# SMC_FrontPanel_ExtensionBoard_Step2_V14_.net
KiCad netlist of a schematic drawn in EAGLE
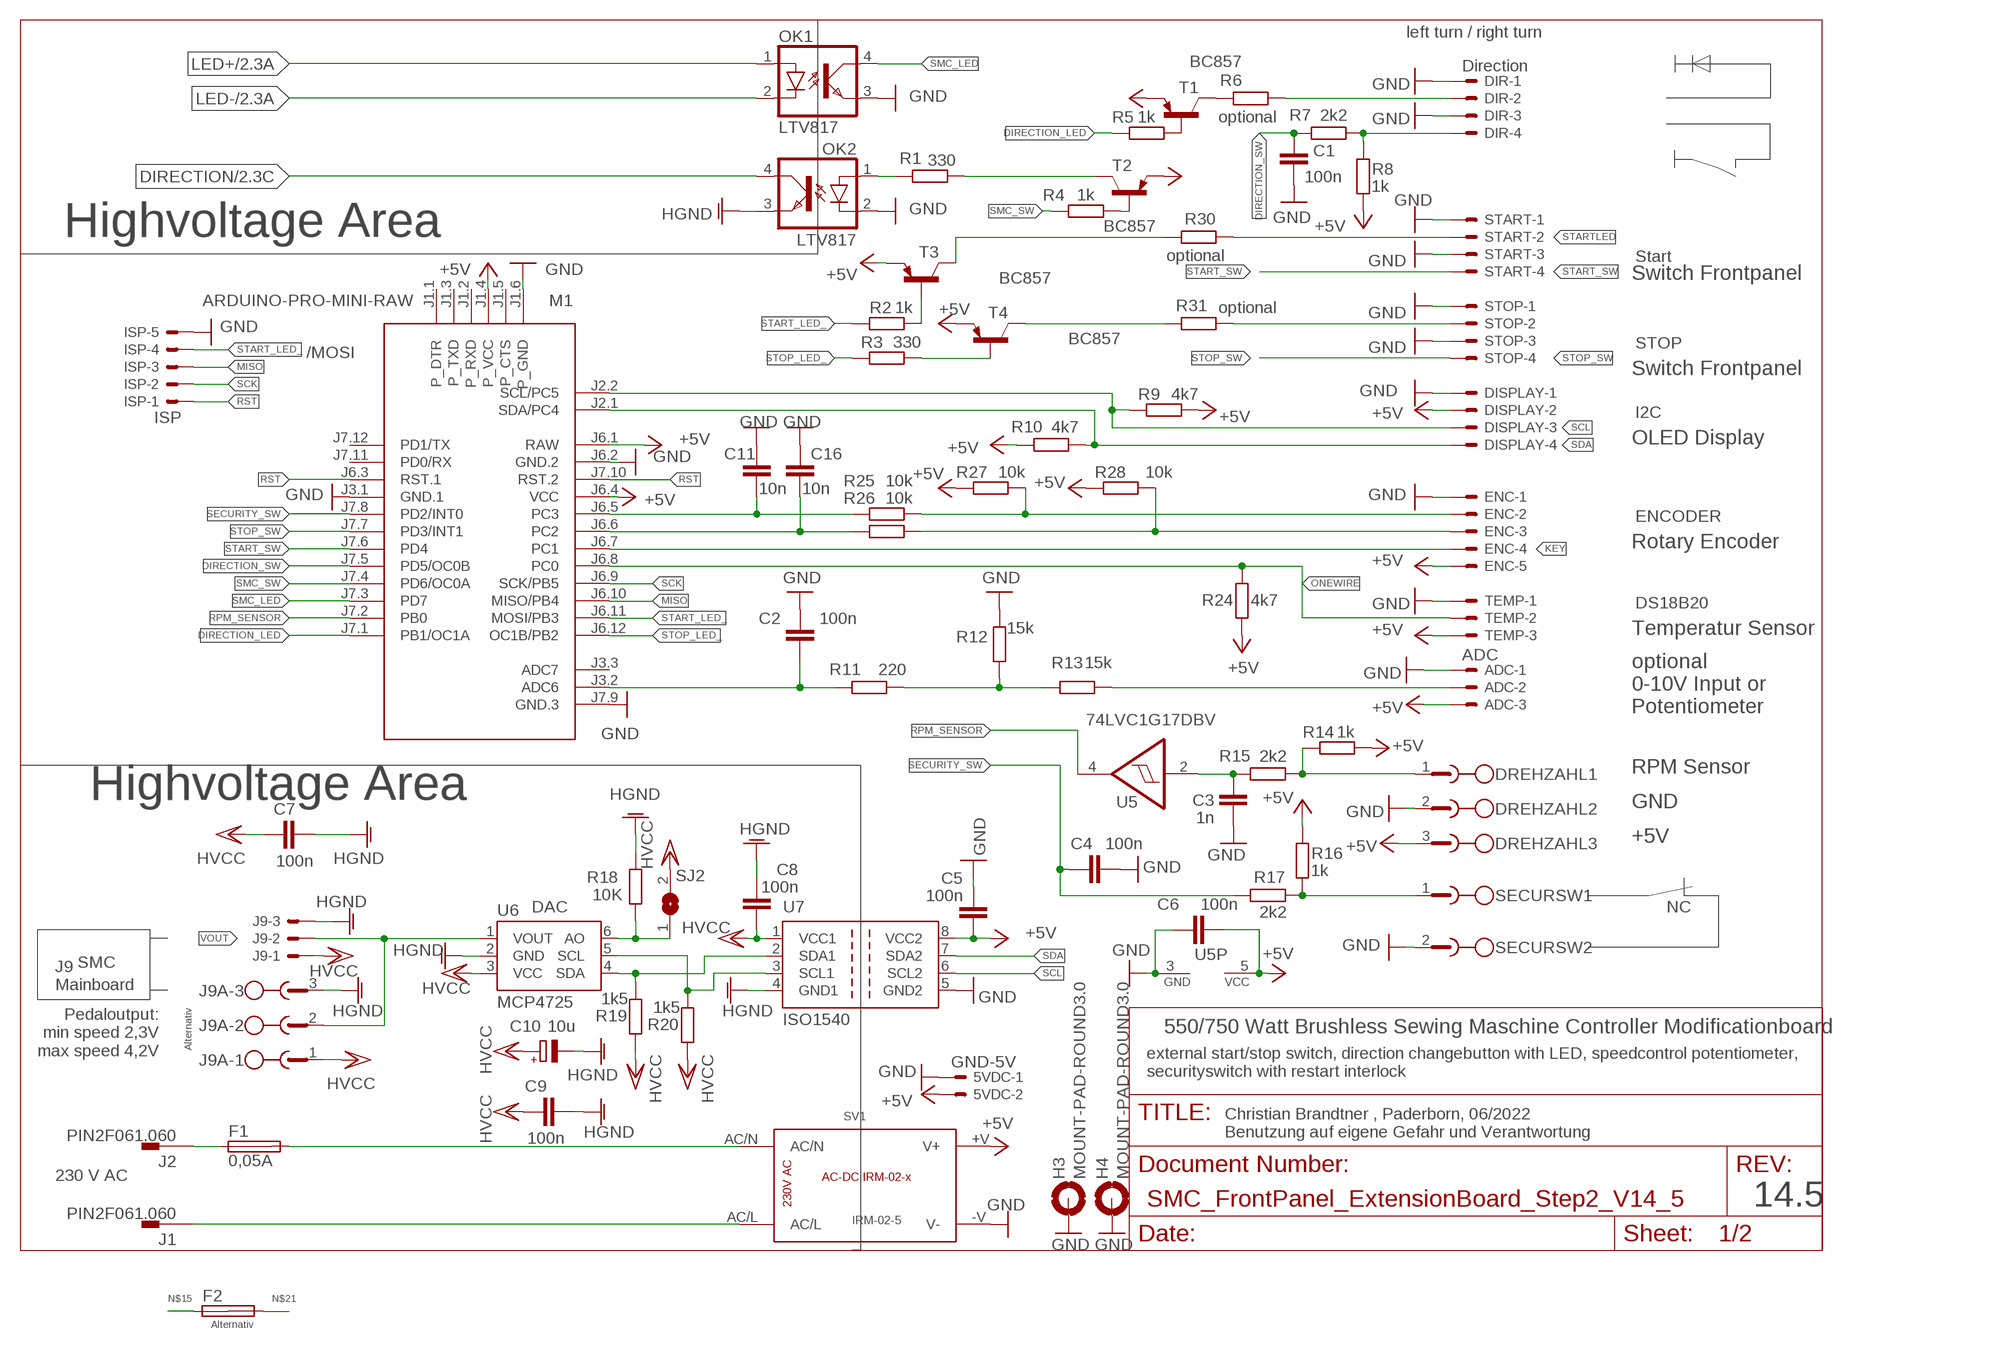
[diagram p0: schematic, sheet 1]
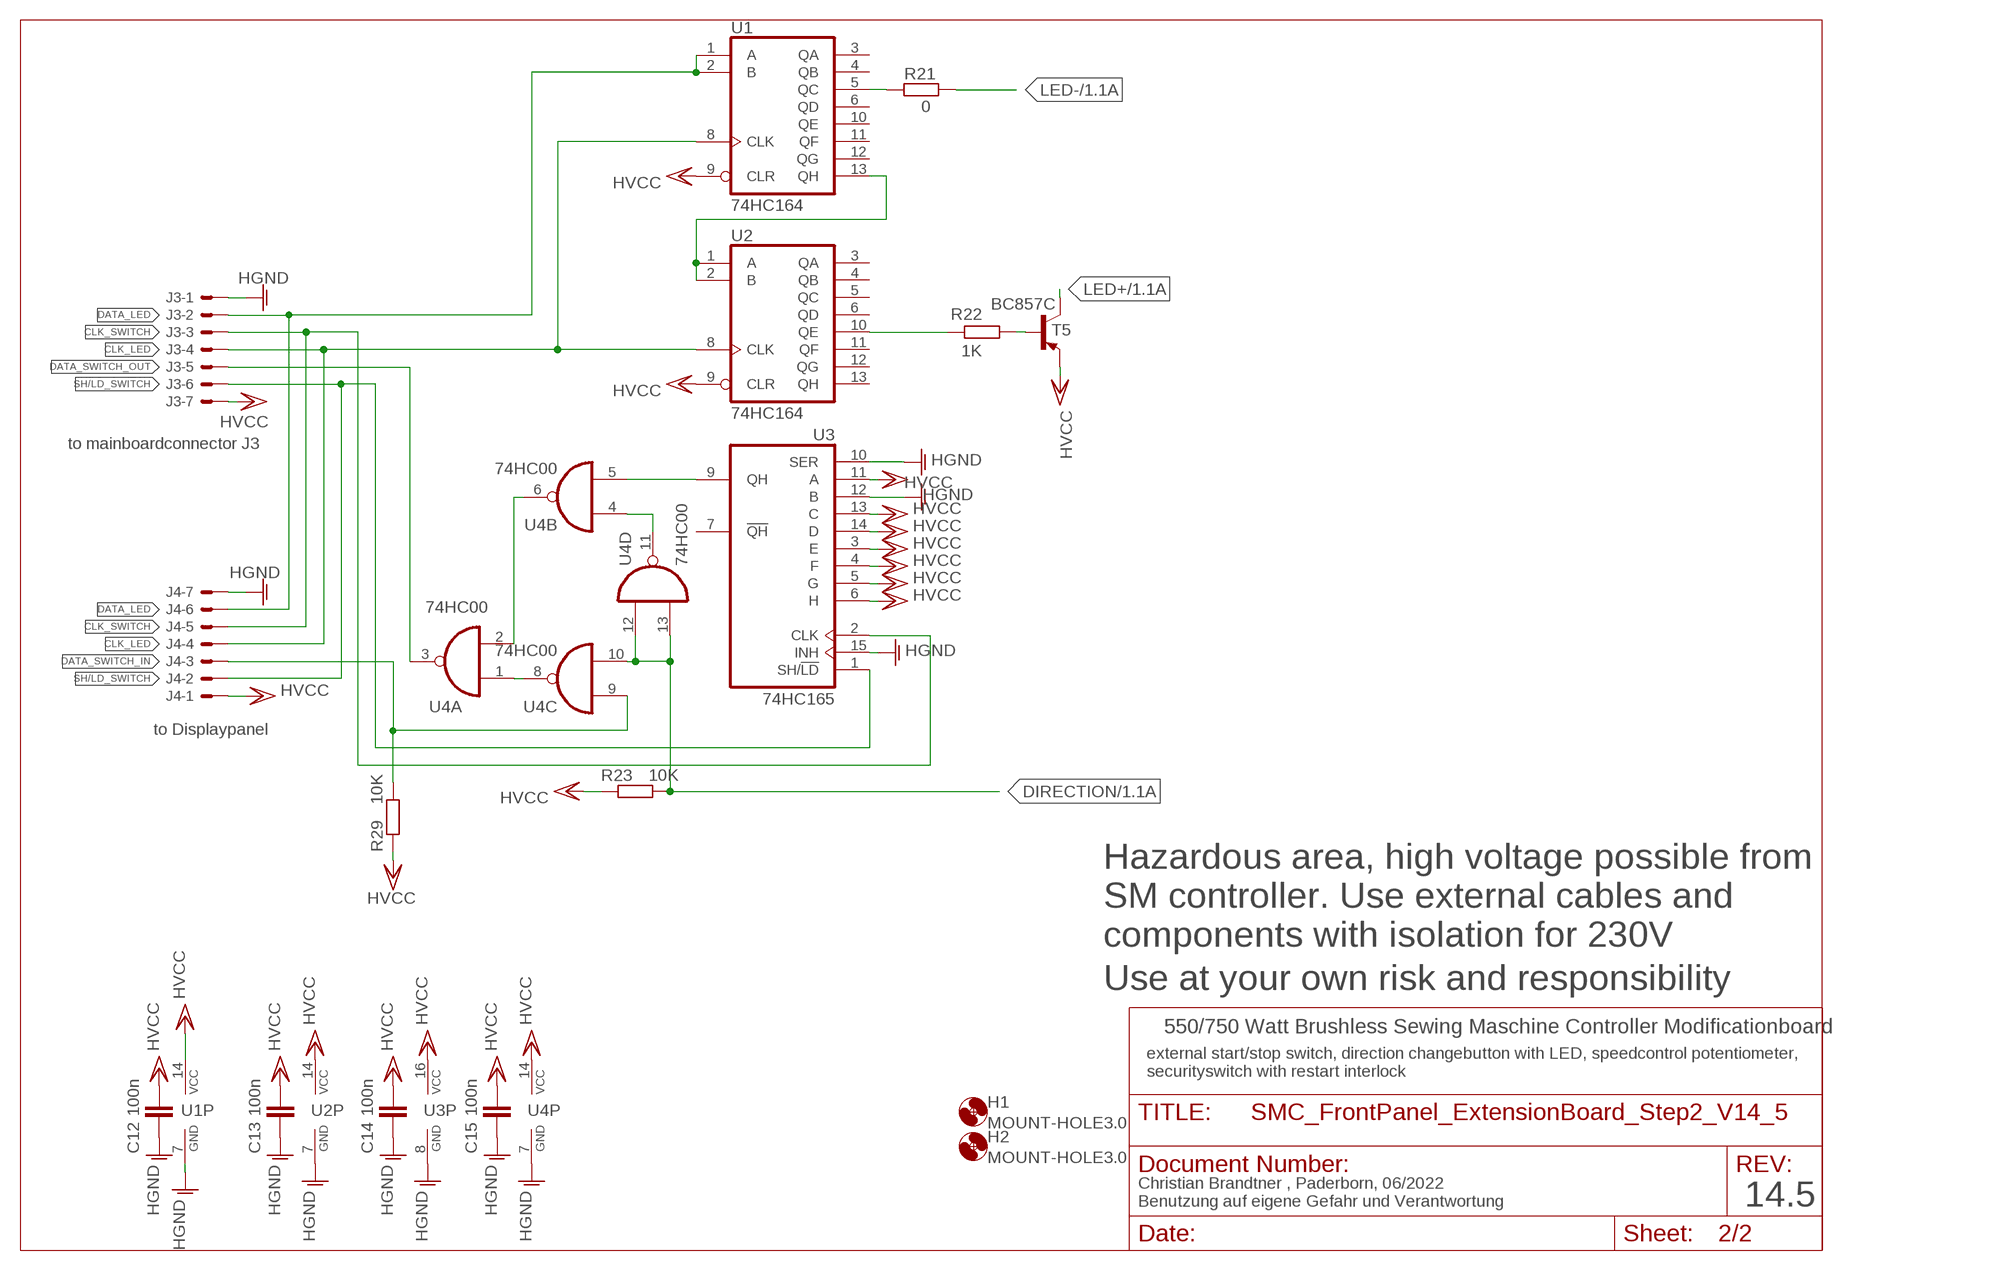
[diagram p1: schematic, sheet 2]

(export (version "E")
  (design (tool "Eeschema 10.0.6"))
  (components
    (comp (ref "C12")
      (value "100n")
      (footprint "eagle-import:C0805")
      (libsource (lib "eagle-import") (part "C-EUC0805"))
    )
    (comp (ref "C13")
      (value "100n")
      (footprint "eagle-import:C0805")
      (libsource (lib "eagle-import") (part "C-EUC0805"))
    )
    (comp (ref "C14")
      (value "100n")
      (footprint "eagle-import:C0805")
      (libsource (lib "eagle-import") (part "C-EUC0805"))
    )
    (comp (ref "C15")
      (value "100n")
      (footprint "eagle-import:C0805")
      (libsource (lib "eagle-import") (part "C-EUC0805"))
    )
    (comp (ref "H1")
      (value "MOUNT-HOLE3.0")
      (footprint "eagle-import:3,0")
      (libsource (lib "eagle-import") (part "MOUNT-HOLE3.0"))
    )
    (comp (ref "H2")
      (value "MOUNT-HOLE3.0")
      (footprint "eagle-import:3,0")
      (libsource (lib "eagle-import") (part "MOUNT-HOLE3.0"))
    )
    (comp (ref "J3")
      (value "to mainboardconnector J3")
      (footprint "eagle-import:JST-XH-07-PACKAGE-ROUND-PAD")
      (libsource (lib "eagle-import") (part "JST-XH-07-PIN-ROUND-PAD"))
    )
    (comp (ref "J4")
      (value "to Displaypanel")
      (footprint "eagle-import:JST-XH-07-PACKAGE-ROUND-PAD")
      (libsource (lib "eagle-import") (part "JST-XH-07-PIN-ROUND-PAD"))
    )
    (comp (ref "R21")
      (value "0")
      (footprint "eagle-import:R0805")
      (libsource (lib "eagle-import") (part "R-EU_R0805"))
    )
    (comp (ref "R22")
      (value "1K")
      (footprint "eagle-import:R0805")
      (libsource (lib "eagle-import") (part "R-EU_R0805"))
    )
    (comp (ref "R23")
      (value "10K")
      (footprint "eagle-import:R0805")
      (libsource (lib "eagle-import") (part "R-EU_R0805"))
    )
    (comp (ref "R29")
      (value "10K")
      (footprint "eagle-import:R0805")
      (libsource (lib "eagle-import") (part "R-EU_R0805"))
    )
    (comp (ref "T5")
      (value "BC857C")
      (footprint "eagle-import:SOT23-BEC")
      (libsource (lib "eagle-import") (part "-PNP-SOT23-BECBC857C"))
    )
    (comp (ref "U1")
      (value "74HC164")
      (footprint "eagle-import:SO14")
      (libsource (lib "eagle-import") (part "74164DHC"))
    )
    (comp (ref "U2")
      (value "74HC164")
      (footprint "eagle-import:SO14")
      (libsource (lib "eagle-import") (part "74164DHC"))
    )
    (comp (ref "U3")
      (value "74HC165")
      (footprint "eagle-import:SO16")
      (libsource (lib "eagle-import") (part "74165DHC"))
    )
    (comp (ref "U4")
      (value "74HC00")
      (footprint "eagle-import:SO14")
      (libsource (lib "eagle-import") (part "7400DHC"))
    )
    (comp (ref "5VDC")
      (value "GND-5V")
      (footprint "eagle-import:JST-XH-02-PACKAGE-ROUND-PAD")
      (libsource (lib "eagle-import") (part "JST-XH-02-PIN-ROUND-PAD"))
    )
    (comp (ref "ADC")
      (value "ADC")
      (footprint "eagle-import:JST-XH-03-PACKAGE-ROUND-PAD")
      (libsource (lib "eagle-import") (part "JST-XH-03-PIN-ROUND-PAD"))
    )
    (comp (ref "C1")
      (value "100n")
      (footprint "eagle-import:C0805")
      (libsource (lib "eagle-import") (part "C-EUC0805"))
    )
    (comp (ref "C2")
      (value "100n")
      (footprint "eagle-import:C0805")
      (libsource (lib "eagle-import") (part "C-EUC0805"))
    )
    (comp (ref "C3")
      (value "1n")
      (footprint "eagle-import:C0805")
      (libsource (lib "eagle-import") (part "C-EUC0805"))
    )
    (comp (ref "C4")
      (value "100n")
      (footprint "eagle-import:C0805")
      (libsource (lib "eagle-import") (part "C-EUC0805"))
    )
    (comp (ref "C5")
      (value "100n")
      (footprint "eagle-import:C0805")
      (libsource (lib "eagle-import") (part "C-EUC0805"))
    )
    (comp (ref "C6")
      (value "100n")
      (footprint "eagle-import:C0805")
      (libsource (lib "eagle-import") (part "C-EUC0805"))
    )
    (comp (ref "C7")
      (value "100n")
      (footprint "eagle-import:C0805")
      (libsource (lib "eagle-import") (part "C-EUC0805"))
    )
    (comp (ref "C8")
      (value "100n")
      (footprint "eagle-import:C0805")
      (libsource (lib "eagle-import") (part "C-EUC0805"))
    )
    (comp (ref "C9")
      (value "100n")
      (footprint "eagle-import:C0805")
      (libsource (lib "eagle-import") (part "C-EUC0805"))
    )
    (comp (ref "C10")
      (value "10u")
      (footprint "eagle-import:153CLV-0405")
      (libsource (lib "eagle-import") (part "CPOL-EU153CLV-0405"))
    )
    (comp (ref "C11")
      (value "10n")
      (footprint "eagle-import:C0805")
      (libsource (lib "eagle-import") (part "C-EUC0805"))
    )
    (comp (ref "C16")
      (value "10n")
      (footprint "eagle-import:C0805")
      (libsource (lib "eagle-import") (part "C-EUC0805"))
    )
    (comp (ref "DIR")
      (value "Direction")
      (footprint "eagle-import:JST-XH-04-PACKAGE-ROUND-PAD")
      (libsource (lib "eagle-import") (part "JST-XH-04-PIN-ROUND-PAD"))
    )
    (comp (ref "DISPLAY")
      (value "I2C")
      (footprint "eagle-import:JST-XH-04-PACKAGE-ROUND-PAD")
      (libsource (lib "eagle-import") (part "JST-XH-04-PIN-ROUND-PAD"))
    )
    (comp (ref "DREHZAHL")
      (value "MCV_1.5/3/-G-3.5")
      (footprint "eagle-import:1843619")
      (libsource (lib "eagle-import") (part "MCV_1.5/3/-G-3.5"))
    )
    (comp (ref "ENC")
      (value "ENCODER")
      (footprint "eagle-import:JST-XH-05-PACKAGE-ROUND-PAD")
      (libsource (lib "eagle-import") (part "JST-XH-05-PIN-ROUND-PAD"))
    )
    (comp (ref "F1")
      (value "0,05A")
      (footprint "eagle-import:MTA501100")
      (libsource (lib "eagle-import") (part "FUSE"))
    )
    (comp (ref "F2")
      (value "SHK20L")
      (footprint "eagle-import:SHK20L")
      (libsource (lib "eagle-import") (part "SHK20L"))
    )
    (comp (ref "H3")
      (value "MOUNT-PAD-ROUND3.0")
      (footprint "eagle-import:3,0-PAD")
      (libsource (lib "eagle-import") (part "MOUNT-PAD-ROUND3.0"))
    )
    (comp (ref "H4")
      (value "MOUNT-PAD-ROUND3.0")
      (footprint "eagle-import:3,0-PAD")
      (libsource (lib "eagle-import") (part "MOUNT-PAD-ROUND3.0"))
    )
    (comp (ref "ISP")
      (value "ISP")
      (footprint "eagle-import:JST-XH-05-PACKAGE-ROUND-PAD")
      (libsource (lib "eagle-import") (part "JST-XH-05-PIN-ROUND-PAD"))
    )
    (comp (ref "J1")
      (value "PIN2F061.060")
      (footprint "eagle-import:F061.060")
      (libsource (lib "eagle-import") (part "PIN2F061.060"))
    )
    (comp (ref "J2")
      (value "PIN2F061.060")
      (footprint "eagle-import:F061.060")
      (libsource (lib "eagle-import") (part "PIN2F061.060"))
    )
    (comp (ref "J9")
      (value "JST-XH-03-PIN-ROUND-PAD")
      (footprint "eagle-import:JST-XH-03-PACKAGE-ROUND-PAD")
      (libsource (lib "eagle-import") (part "JST-XH-03-PIN-ROUND-PAD"))
    )
    (comp (ref "J9A-")
      (value "MCV_1.5/3/-G-3.5")
      (footprint "eagle-import:1843619")
      (libsource (lib "eagle-import") (part "MCV_1.5/3/-G-3.5"))
    )
    (comp (ref "M1")
      (value "ARDUINO-PRO-MINI-RAW")
      (footprint "eagle-import:ARDUINO-PRO-MINI")
      (libsource (lib "eagle-import") (part "ARDUINO-PRO-MINI-RAW"))
    )
    (comp (ref "OK1")
      (value "LTV817")
      (footprint "eagle-import:SMD4-7")
      (fields (field (name "MF") "VISHAY/TELEFUNKEN") (field (name "MPN") "SFH6186-2"))
      (libsource (lib "eagle-import") (part "SFH618?6-2"))
    )
    (comp (ref "OK2")
      (value "LTV817")
      (footprint "eagle-import:SMD4-7")
      (fields (field (name "MF") "VISHAY/TELEFUNKEN") (field (name "MPN") "SFH6186-2"))
      (libsource (lib "eagle-import") (part "SFH618?6-2"))
    )
    (comp (ref "R1")
      (value "330")
      (footprint "eagle-import:R0805")
      (libsource (lib "eagle-import") (part "R-EU_R0805"))
    )
    (comp (ref "R2")
      (value "1k")
      (footprint "eagle-import:R0805")
      (libsource (lib "eagle-import") (part "R-EU_R0805"))
    )
    (comp (ref "R3")
      (value "330")
      (footprint "eagle-import:R0805")
      (libsource (lib "eagle-import") (part "R-EU_R0805"))
    )
    (comp (ref "R4")
      (value "1k")
      (footprint "eagle-import:R0805")
      (libsource (lib "eagle-import") (part "R-EU_R0805"))
    )
    (comp (ref "R5")
      (value "1k")
      (footprint "eagle-import:R0805")
      (libsource (lib "eagle-import") (part "R-EU_R0805"))
    )
    (comp (ref "R6")
      (value "optional")
      (footprint "eagle-import:R0805")
      (libsource (lib "eagle-import") (part "R-EU_R0805"))
    )
    (comp (ref "R7")
      (value "2k2")
      (footprint "eagle-import:R0805")
      (libsource (lib "eagle-import") (part "R-EU_R0805"))
    )
    (comp (ref "R8")
      (value "1k")
      (footprint "eagle-import:R0805")
      (libsource (lib "eagle-import") (part "R-EU_R0805"))
    )
    (comp (ref "R9")
      (value "4k7")
      (footprint "eagle-import:R0805")
      (libsource (lib "eagle-import") (part "R-EU_R0805"))
    )
    (comp (ref "R10")
      (value "4k7")
      (footprint "eagle-import:R0805")
      (libsource (lib "eagle-import") (part "R-EU_R0805"))
    )
    (comp (ref "R11")
      (value "220")
      (footprint "eagle-import:R0805")
      (libsource (lib "eagle-import") (part "R-EU_R0805"))
    )
    (comp (ref "R12")
      (value "15k")
      (footprint "eagle-import:R0805")
      (libsource (lib "eagle-import") (part "R-EU_R0805"))
    )
    (comp (ref "R13")
      (value "15k")
      (footprint "eagle-import:R0805")
      (libsource (lib "eagle-import") (part "R-EU_R0805"))
    )
    (comp (ref "R14")
      (value "1k")
      (footprint "eagle-import:R0805")
      (libsource (lib "eagle-import") (part "R-EU_R0805"))
    )
    (comp (ref "R15")
      (value "2k2")
      (footprint "eagle-import:R0805")
      (libsource (lib "eagle-import") (part "R-EU_R0805"))
    )
    (comp (ref "R16")
      (value "1k")
      (footprint "eagle-import:R0805")
      (libsource (lib "eagle-import") (part "R-EU_R0805"))
    )
    (comp (ref "R17")
      (value "2k2")
      (footprint "eagle-import:R0805")
      (libsource (lib "eagle-import") (part "R-EU_R0805"))
    )
    (comp (ref "R18")
      (value "10K")
      (footprint "eagle-import:R0805")
      (libsource (lib "eagle-import") (part "R-EU_R0805"))
    )
    (comp (ref "R19")
      (value "1k5")
      (footprint "eagle-import:R0805")
      (libsource (lib "eagle-import") (part "R-EU_R0805"))
    )
    (comp (ref "R20")
      (value "1k5")
      (footprint "eagle-import:R0805")
      (libsource (lib "eagle-import") (part "R-EU_R0805"))
    )
    (comp (ref "R24")
      (value "4k7")
      (footprint "eagle-import:R0805")
      (libsource (lib "eagle-import") (part "R-EU_R0805"))
    )
    (comp (ref "R25")
      (value "10k")
      (footprint "eagle-import:R0805")
      (libsource (lib "eagle-import") (part "R-EU_R0805"))
    )
    (comp (ref "R26")
      (value "10k")
      (footprint "eagle-import:R0805")
      (libsource (lib "eagle-import") (part "R-EU_R0805"))
    )
    (comp (ref "R27")
      (value "10k")
      (footprint "eagle-import:R0805")
      (libsource (lib "eagle-import") (part "R-EU_R0805"))
    )
    (comp (ref "R28")
      (value "10k")
      (footprint "eagle-import:R0805")
      (libsource (lib "eagle-import") (part "R-EU_R0805"))
    )
    (comp (ref "R30")
      (value "optional")
      (footprint "eagle-import:R0805")
      (libsource (lib "eagle-import") (part "R-EU_R0805"))
    )
    (comp (ref "R31")
      (value "optional")
      (footprint "eagle-import:R0805")
      (libsource (lib "eagle-import") (part "R-EU_R0805"))
    )
    (comp (ref "SECURSW")
      (value "MCV_1,5/2-G-3,5")
      (footprint "eagle-import:1843606")
      (libsource (lib "eagle-import") (part "MCV_1,5/2-G-3,5"))
    )
    (comp (ref "SJ2") (value "SJ") (footprint "eagle-import:SJ") (libsource (lib "eagle-import") (part "SJ")))
    (comp (ref "START")
      (value "Start")
      (footprint "eagle-import:JST-XH-04-PACKAGE-ROUND-PAD")
      (libsource (lib "eagle-import") (part "JST-XH-04-PIN-ROUND-PAD"))
    )
    (comp (ref "STOP")
      (value "STOP")
      (footprint "eagle-import:JST-XH-04-PACKAGE-ROUND-PAD")
      (libsource (lib "eagle-import") (part "JST-XH-04-PIN-ROUND-PAD"))
    )
    (comp (ref "SV1")
      (value "IRM-02-5")
      (footprint "eagle-import:IRM-02-X")
      (libsource (lib "eagle-import") (part "IRM-02-X"))
    )
    (comp (ref "T1")
      (value "BC857")
      (footprint "eagle-import:SOT23-BEC")
      (libsource (lib "eagle-import") (part "BC857SMDA"))
    )
    (comp (ref "T2")
      (value "BC857")
      (footprint "eagle-import:SOT23-BEC")
      (libsource (lib "eagle-import") (part "BC857SMDA"))
    )
    (comp (ref "T3")
      (value "BC857")
      (footprint "eagle-import:SOT23-BEC")
      (libsource (lib "eagle-import") (part "BC857SMDA"))
    )
    (comp (ref "T4")
      (value "BC857")
      (footprint "eagle-import:SOT23-BEC")
      (libsource (lib "eagle-import") (part "BC857SMDA"))
    )
    (comp (ref "TEMP")
      (value "DS18B20")
      (footprint "eagle-import:JST-XH-03-PACKAGE-ROUND-PAD")
      (libsource (lib "eagle-import") (part "JST-XH-03-PIN-ROUND-PAD"))
    )
    (comp (ref "U5")
      (value "74LVC1G17DBV")
      (footprint "eagle-import:SOT23-5")
      (libsource (lib "eagle-import") (part "741G17DBVLVC"))
    )
    (comp (ref "U6")
      (value "MCP4725")
      (footprint "eagle-import:SOT23-6")
      (libsource (lib "eagle-import") (part "MCP4725SOT-23"))
    )
    (comp (ref "U7")
      (value "ISO1540")
      (footprint "eagle-import:SO-08")
      (libsource (lib "eagle-import") (part "ISO1540"))
    )
  )
  (nets
    (net (code "1") (name "+5V") (class "Default")
      (node (ref "5VDC") (pin "2") (pinfunction "S_2") (pintype "passive"))
      (node (ref "ADC") (pin "3") (pinfunction "S_3") (pintype "passive"))
      (node (ref "C5") (pin "1") (pinfunction "1_1") (pintype "passive"))
      (node (ref "C6") (pin "1") (pinfunction "1_1") (pintype "passive"))
      (node (ref "DISPLAY") (pin "2") (pinfunction "S_2") (pintype "passive"))
      (node (ref "DREHZAHL") (pin "3") (pinfunction "1_3") (pintype "passive"))
      (node (ref "ENC") (pin "5") (pinfunction "S_5") (pintype "passive"))
      (node (ref "M1") (pin "J1.4") (pinfunction "P_VCC_J1.4") (pintype "bidirectional"))
      (node (ref "M1") (pin "J6.1") (pinfunction "RAW_J6.1") (pintype "power_in"))
      (node (ref "M1") (pin "J6.4") (pinfunction "VCC_J6.4") (pintype "power_in"))
      (node (ref "R10") (pin "1") (pinfunction "1_1") (pintype "passive"))
      (node (ref "R14") (pin "1") (pinfunction "1_1") (pintype "passive"))
      (node (ref "R16") (pin "1") (pinfunction "1_1") (pintype "passive"))
      (node (ref "R24") (pin "2") (pinfunction "2_2") (pintype "passive"))
      (node (ref "R27") (pin "1") (pinfunction "1_1") (pintype "passive"))
      (node (ref "R28") (pin "1") (pinfunction "1_1") (pintype "passive"))
      (node (ref "R8") (pin "2") (pinfunction "2_2") (pintype "passive"))
      (node (ref "R9") (pin "1") (pinfunction "1_1") (pintype "passive"))
      (node (ref "SV1") (pin "+V") (pinfunction "V+_+V") (pintype "bidirectional"))
      (node (ref "T1") (pin "E") (pinfunction "E_E") (pintype "passive"))
      (node (ref "T2") (pin "E") (pinfunction "E_E") (pintype "passive"))
      (node (ref "T3") (pin "E") (pinfunction "E_E") (pintype "passive"))
      (node (ref "T4") (pin "E") (pinfunction "E_E") (pintype "passive"))
      (node (ref "TEMP") (pin "3") (pinfunction "S_3") (pintype "passive"))
      (node (ref "U5") (pin "5") (pinfunction "VCC_5") (pintype "power_in"))
      (node (ref "U7") (pin "8") (pinfunction "VCC2_8") (pintype "power_in"))
    )
    (net (code "2") (name "CLK_LED") (class "Default")
      (node (ref "J3") (pin "4") (pinfunction "S_4") (pintype "passive"))
      (node (ref "J4") (pin "4") (pinfunction "S_4") (pintype "passive"))
      (node (ref "U1") (pin "8") (pinfunction "CLK_8") (pintype "input"))
      (node (ref "U2") (pin "8") (pinfunction "CLK_8") (pintype "input"))
    )
    (net (code "3") (name "CLK_SWITCH") (class "Default")
      (node (ref "J3") (pin "3") (pinfunction "S_3") (pintype "passive"))
      (node (ref "J4") (pin "5") (pinfunction "S_5") (pintype "passive"))
      (node (ref "U3") (pin "2") (pinfunction "CLK_2") (pintype "input"))
    )
    (net (code "4") (name "DATA_LED") (class "Default")
      (node (ref "J3") (pin "2") (pinfunction "S_2") (pintype "passive"))
      (node (ref "J4") (pin "6") (pinfunction "S_6") (pintype "passive"))
      (node (ref "U1") (pin "1") (pinfunction "A_1") (pintype "input"))
      (node (ref "U1") (pin "2") (pinfunction "B_2") (pintype "input"))
    )
    (net (code "5") (name "DATA_SWITCH_IN") (class "Default")
      (node (ref "J4") (pin "3") (pinfunction "S_3") (pintype "passive"))
      (node (ref "R29") (pin "1") (pinfunction "1_1") (pintype "passive"))
      (node (ref "U4") (pin "9") (pinfunction "I0_9") (pintype "input"))
    )
    (net (code "6") (name "DATA_SWITCH_OUT") (class "Default")
      (node (ref "J3") (pin "5") (pinfunction "S_5") (pintype "passive"))
      (node (ref "U4") (pin "3") (pinfunction "O_3") (pintype "output"))
    )
    (net (code "7") (name "DIRECTION") (class "Default")
      (node (ref "OK2") (pin "4") (pinfunction "COL_4") (pintype "passive"))
      (node (ref "R23") (pin "1") (pinfunction "1_1") (pintype "passive"))
      (node (ref "U4") (pin "10") (pinfunction "I1_10") (pintype "input"))
      (node (ref "U4") (pin "12") (pinfunction "I0_12") (pintype "input"))
      (node (ref "U4") (pin "13") (pinfunction "I1_13") (pintype "input"))
    )
    (net (code "8") (name "DIRECTION_LED") (class "Default")
      (node (ref "M1") (pin "J7.1") (pinfunction "PB1/OC1A_J7.1") (pintype "bidirectional"))
      (node (ref "R5") (pin "2") (pinfunction "2_2") (pintype "passive"))
    )
    (net (code "9") (name "DIRECTION_SW") (class "Default")
      (node (ref "C1") (pin "2") (pinfunction "2_2") (pintype "passive"))
      (node (ref "M1") (pin "J7.5") (pinfunction "PD5/OC0B_J7.5") (pintype "bidirectional"))
      (node (ref "R7") (pin "1") (pinfunction "1_1") (pintype "passive"))
    )
    (net (code "10") (name "GND") (class "Default")
      (node (ref "5VDC") (pin "1") (pinfunction "S_1") (pintype "passive"))
      (node (ref "ADC") (pin "1") (pinfunction "S_1") (pintype "passive"))
      (node (ref "C1") (pin "1") (pinfunction "1_1") (pintype "passive"))
      (node (ref "C11") (pin "2") (pinfunction "2_2") (pintype "passive"))
      (node (ref "C16") (pin "2") (pinfunction "2_2") (pintype "passive"))
      (node (ref "C2") (pin "2") (pinfunction "2_2") (pintype "passive"))
      (node (ref "C3") (pin "1") (pinfunction "1_1") (pintype "passive"))
      (node (ref "C4") (pin "2") (pinfunction "2_2") (pintype "passive"))
      (node (ref "C5") (pin "2") (pinfunction "2_2") (pintype "passive"))
      (node (ref "C6") (pin "2") (pinfunction "2_2") (pintype "passive"))
      (node (ref "DIR") (pin "1") (pinfunction "S_1") (pintype "passive"))
      (node (ref "DIR") (pin "3") (pinfunction "S_3") (pintype "passive"))
      (node (ref "DISPLAY") (pin "1") (pinfunction "S_1") (pintype "passive"))
      (node (ref "DREHZAHL") (pin "2") (pinfunction "1_2") (pintype "passive"))
      (node (ref "ENC") (pin "1") (pinfunction "S_1") (pintype "passive"))
      (node (ref "H3") (pin "B3,0") (pinfunction "MOUNT_B3,0") (pintype "passive"))
      (node (ref "H4") (pin "B3,0") (pinfunction "MOUNT_B3,0") (pintype "passive"))
      (node (ref "ISP") (pin "5") (pinfunction "S_5") (pintype "passive"))
      (node (ref "M1") (pin "J1.6") (pinfunction "P_GND_J1.6") (pintype "bidirectional"))
      (node (ref "M1") (pin "J3.1") (pinfunction "GND.1_J3.1") (pintype "power_in"))
      (node (ref "M1") (pin "J6.2") (pinfunction "GND.2_J6.2") (pintype "power_in"))
      (node (ref "M1") (pin "J7.9") (pinfunction "GND.3_J7.9") (pintype "bidirectional"))
      (node (ref "OK1") (pin "3") (pinfunction "EMIT_3") (pintype "passive"))
      (node (ref "OK2") (pin "2") (pinfunction "C_2") (pintype "passive"))
      (node (ref "R12") (pin "2") (pinfunction "2_2") (pintype "passive"))
      (node (ref "SECURSW") (pin "2") (pinfunction "1_2") (pintype "passive"))
      (node (ref "START") (pin "1") (pinfunction "S_1") (pintype "passive"))
      (node (ref "START") (pin "3") (pinfunction "S_3") (pintype "passive"))
      (node (ref "STOP") (pin "1") (pinfunction "S_1") (pintype "passive"))
      (node (ref "STOP") (pin "3") (pinfunction "S_3") (pintype "passive"))
      (node (ref "SV1") (pin "-V") (pinfunction "V-_-V") (pintype "bidirectional"))
      (node (ref "TEMP") (pin "1") (pinfunction "S_1") (pintype "passive"))
      (node (ref "U5") (pin "3") (pinfunction "GND_3") (pintype "power_in"))
      (node (ref "U7") (pin "5") (pinfunction "GND2_5") (pintype "power_in"))
    )
    (net (code "11") (name "HGND") (class "Default")
      (node (ref "C10") (pin "-") (pinfunction "-_-") (pintype "passive"))
      (node (ref "C12") (pin "1") (pinfunction "1_1") (pintype "passive"))
      (node (ref "C13") (pin "1") (pinfunction "1_1") (pintype "passive"))
      (node (ref "C14") (pin "1") (pinfunction "1_1") (pintype "passive"))
      (node (ref "C15") (pin "1") (pinfunction "1_1") (pintype "passive"))
      (node (ref "C7") (pin "1") (pinfunction "1_1") (pintype "passive"))
      (node (ref "C8") (pin "2") (pinfunction "2_2") (pintype "passive"))
      (node (ref "C9") (pin "1") (pinfunction "1_1") (pintype "passive"))
      (node (ref "J3") (pin "1") (pinfunction "S_1") (pintype "passive"))
      (node (ref "J4") (pin "7") (pinfunction "S_7") (pintype "passive"))
      (node (ref "J9") (pin "3") (pinfunction "S_3") (pintype "passive"))
      (node (ref "J9A-") (pin "3") (pinfunction "1_3") (pintype "passive"))
      (node (ref "OK2") (pin "3") (pinfunction "EMIT_3") (pintype "passive"))
      (node (ref "R18") (pin "1") (pinfunction "1_1") (pintype "passive"))
      (node (ref "U1") (pin "7") (pinfunction "GND_7") (pintype "power_in"))
      (node (ref "U2") (pin "7") (pinfunction "GND_7") (pintype "power_in"))
      (node (ref "U3") (pin "10") (pinfunction "SER_10") (pintype "input"))
      (node (ref "U3") (pin "12") (pinfunction "B_12") (pintype "input"))
      (node (ref "U3") (pin "15") (pinfunction "INH_15") (pintype "input"))
      (node (ref "U3") (pin "8") (pinfunction "GND_8") (pintype "power_in"))
      (node (ref "U4") (pin "7") (pinfunction "GND_7") (pintype "power_in"))
      (node (ref "U6") (pin "2") (pinfunction "GND_2") (pintype "bidirectional"))
      (node (ref "U7") (pin "4") (pinfunction "GND1_4") (pintype "power_in"))
    )
    (net (code "12") (name "HVCC") (class "Default")
      (node (ref "C10") (pin "+") (pinfunction "+_+") (pintype "passive"))
      (node (ref "C12") (pin "2") (pinfunction "2_2") (pintype "passive"))
      (node (ref "C13") (pin "2") (pinfunction "2_2") (pintype "passive"))
      (node (ref "C14") (pin "2") (pinfunction "2_2") (pintype "passive"))
      (node (ref "C15") (pin "2") (pinfunction "2_2") (pintype "passive"))
      (node (ref "C7") (pin "2") (pinfunction "2_2") (pintype "passive"))
      (node (ref "C8") (pin "1") (pinfunction "1_1") (pintype "passive"))
      (node (ref "C9") (pin "2") (pinfunction "2_2") (pintype "passive"))
      (node (ref "J3") (pin "7") (pinfunction "S_7") (pintype "passive"))
      (node (ref "J4") (pin "1") (pinfunction "S_1") (pintype "passive"))
      (node (ref "J9") (pin "1") (pinfunction "S_1") (pintype "passive"))
      (node (ref "J9A-") (pin "1") (pinfunction "1_1") (pintype "passive"))
      (node (ref "R19") (pin "2") (pinfunction "2_2") (pintype "passive"))
      (node (ref "R20") (pin "2") (pinfunction "2_2") (pintype "passive"))
      (node (ref "R23") (pin "2") (pinfunction "2_2") (pintype "passive"))
      (node (ref "R29") (pin "2") (pinfunction "2_2") (pintype "passive"))
      (node (ref "SJ2") (pin "2") (pinfunction "2_2") (pintype "passive"))
      (node (ref "T5") (pin "E") (pinfunction "E_E") (pintype "passive"))
      (node (ref "U1") (pin "14") (pinfunction "VCC_14") (pintype "power_in"))
      (node (ref "U1") (pin "9") (pinfunction "CLR_9") (pintype "input"))
      (node (ref "U2") (pin "14") (pinfunction "VCC_14") (pintype "power_in"))
      (node (ref "U2") (pin "9") (pinfunction "CLR_9") (pintype "input"))
      (node (ref "U3") (pin "11") (pinfunction "A_11") (pintype "input"))
      (node (ref "U3") (pin "13") (pinfunction "C_13") (pintype "input"))
      (node (ref "U3") (pin "14") (pinfunction "D_14") (pintype "input"))
      (node (ref "U3") (pin "16") (pinfunction "VCC_16") (pintype "power_in"))
      (node (ref "U3") (pin "3") (pinfunction "E_3") (pintype "input"))
      (node (ref "U3") (pin "4") (pinfunction "F_4") (pintype "input"))
      (node (ref "U3") (pin "5") (pinfunction "G_5") (pintype "input"))
      (node (ref "U3") (pin "6") (pinfunction "H_6") (pintype "input"))
      (node (ref "U4") (pin "14") (pinfunction "VCC_14") (pintype "power_in"))
      (node (ref "U6") (pin "3") (pinfunction "VCC_3") (pintype "bidirectional"))
      (node (ref "U7") (pin "1") (pinfunction "VCC1_1") (pintype "power_in"))
    )
    (net (code "13") (name "KEY") (class "Default")
      (node (ref "ENC") (pin "4") (pinfunction "S_4") (pintype "passive"))
      (node (ref "M1") (pin "J6.7") (pinfunction "PC1_J6.7") (pintype "bidirectional"))
    )
    (net (code "14") (name "LED+") (class "Default")
      (node (ref "OK1") (pin "1") (pinfunction "A_1") (pintype "passive"))
      (node (ref "T5") (pin "C") (pinfunction "C_C") (pintype "passive"))
    )
    (net (code "15") (name "LED-") (class "Default")
      (node (ref "OK1") (pin "2") (pinfunction "C_2") (pintype "passive"))
      (node (ref "R21") (pin "2") (pinfunction "2_2") (pintype "passive"))
    )
    (net (code "16") (name "MISO") (class "Default")
      (node (ref "ISP") (pin "3") (pinfunction "S_3") (pintype "passive"))
      (node (ref "M1") (pin "J6.10") (pinfunction "MISO/PB4_J6.10") (pintype "bidirectional"))
    )
    (net (code "17") (name "N$15") (class "Default")
      (node (ref "F1") (pin "1") (pinfunction "1_1") (pintype "passive"))
      (node (ref "F2") (pin "1A") (pinfunction "1A_1A") (pintype "passive"))
      (node (ref "J2") (pin "A1") (pinfunction "1_A1") (pintype "passive"))
      (node (ref "J2") (pin "A2") (pinfunction "1_A2") (pintype "passive"))
    )
    (net (code "18") (name "N$21") (class "Default")
      (node (ref "F1") (pin "2") (pinfunction "2_2") (pintype "passive"))
      (node (ref "F2") (pin "2A") (pinfunction "2A_2A") (pintype "passive"))
      (node (ref "SV1") (pin "AC/N") (pinfunction "AC/N_AC/N") (pintype "bidirectional"))
    )
    (net (code "19") (name "Net-(ADCB-S)") (class "Default")
      (node (ref "ADC") (pin "2") (pinfunction "S_2") (pintype "passive"))
      (node (ref "R13") (pin "1") (pinfunction "1_1") (pintype "passive"))
    )
    (net (code "20") (name "Net-(DIRB-S)") (class "Default")
      (node (ref "DIR") (pin "2") (pinfunction "S_2") (pintype "passive"))
      (node (ref "R6") (pin "1") (pinfunction "1_1") (pintype "passive"))
    )
    (net (code "21") (name "Net-(DIRD-S)") (class "Default")
      (node (ref "DIR") (pin "4") (pinfunction "S_4") (pintype "passive"))
      (node (ref "R7") (pin "2") (pinfunction "2_2") (pintype "passive"))
      (node (ref "R8") (pin "1") (pinfunction "1_1") (pintype "passive"))
    )
    (net (code "22") (name "Net-(DREHZAHL-Pad1)") (class "Default")
      (node (ref "DREHZAHL") (pin "1") (pinfunction "1_1") (pintype "passive"))
      (node (ref "R14") (pin "2") (pinfunction "2_2") (pintype "passive"))
      (node (ref "R15") (pin "2") (pinfunction "2_2") (pintype "passive"))
    )
    (net (code "23") (name "Net-(ENCB-S)") (class "Default")
      (node (ref "ENC") (pin "2") (pinfunction "S_2") (pintype "passive"))
      (node (ref "R25") (pin "2") (pinfunction "2_2") (pintype "passive"))
      (node (ref "R27") (pin "2") (pinfunction "2_2") (pintype "passive"))
    )
    (net (code "24") (name "Net-(ENCC-S)") (class "Default")
      (node (ref "ENC") (pin "3") (pinfunction "S_3") (pintype "passive"))
      (node (ref "R26") (pin "2") (pinfunction "2_2") (pintype "passive"))
      (node (ref "R28") (pin "2") (pinfunction "2_2") (pintype "passive"))
    )
    (net (code "25") (name "Net-(J1-1-PadA1)") (class "Default")
      (node (ref "J1") (pin "A1") (pinfunction "1_A1") (pintype "passive"))
      (node (ref "J1") (pin "A2") (pinfunction "1_A2") (pintype "passive"))
      (node (ref "SV1") (pin "AC/L") (pinfunction "AC/L_AC/L") (pintype "bidirectional"))
    )
    (net (code "26") (name "Net-(M1-ADC6)") (class "Default")
      (node (ref "C2") (pin "1") (pinfunction "1_1") (pintype "passive"))
      (node (ref "M1") (pin "J3.2") (pinfunction "ADC6_J3.2") (pintype "bidirectional"))
      (node (ref "R11") (pin "1") (pinfunction "1_1") (pintype "passive"))
    )
    (net (code "27") (name "Net-(M1-PC2)") (class "Default")
      (node (ref "C16") (pin "1") (pinfunction "1_1") (pintype "passive"))
      (node (ref "M1") (pin "J6.6") (pinfunction "PC2_J6.6") (pintype "bidirectional"))
      (node (ref "R26") (pin "1") (pinfunction "1_1") (pintype "passive"))
    )
    (net (code "28") (name "Net-(M1-PC3)") (class "Default")
      (node (ref "C11") (pin "1") (pinfunction "1_1") (pintype "passive"))
      (node (ref "M1") (pin "J6.5") (pinfunction "PC3_J6.5") (pintype "bidirectional"))
      (node (ref "R25") (pin "1") (pinfunction "1_1") (pintype "passive"))
    )
    (net (code "29") (name "Net-(OK2-A)") (class "Default")
      (node (ref "OK2") (pin "1") (pinfunction "A_1") (pintype "passive"))
      (node (ref "R1") (pin "2") (pinfunction "2_2") (pintype "passive"))
    )
    (net (code "30") (name "Net-(R1-Pad1)") (class "Default")
      (node (ref "R1") (pin "1") (pinfunction "1_1") (pintype "passive"))
      (node (ref "T2") (pin "C") (pinfunction "C_C") (pintype "passive"))
    )
    (net (code "31") (name "Net-(R2-Pad1)") (class "Default")
      (node (ref "R2") (pin "1") (pinfunction "1_1") (pintype "passive"))
      (node (ref "T3") (pin "B") (pinfunction "B_B") (pintype "passive"))
    )
    (net (code "32") (name "Net-(R3-Pad1)") (class "Default")
      (node (ref "R3") (pin "1") (pinfunction "1_1") (pintype "passive"))
      (node (ref "T4") (pin "B") (pinfunction "B_B") (pintype "passive"))
    )
    (net (code "33") (name "Net-(R4-Pad1)") (class "Default")
      (node (ref "R4") (pin "1") (pinfunction "1_1") (pintype "passive"))
      (node (ref "T2") (pin "B") (pinfunction "B_B") (pintype "passive"))
    )
    (net (code "34") (name "Net-(R5-Pad1)") (class "Default")
      (node (ref "R5") (pin "1") (pinfunction "1_1") (pintype "passive"))
      (node (ref "T1") (pin "B") (pinfunction "B_B") (pintype "passive"))
    )
    (net (code "35") (name "Net-(R6-Pad2)") (class "Default")
      (node (ref "R6") (pin "2") (pinfunction "2_2") (pintype "passive"))
      (node (ref "T1") (pin "C") (pinfunction "C_C") (pintype "passive"))
    )
    (net (code "36") (name "Net-(R11-Pad2)") (class "Default")
      (node (ref "R11") (pin "2") (pinfunction "2_2") (pintype "passive"))
      (node (ref "R12") (pin "1") (pinfunction "1_1") (pintype "passive"))
      (node (ref "R13") (pin "2") (pinfunction "2_2") (pintype "passive"))
    )
    (net (code "37") (name "Net-(R16-Pad2)") (class "Default")
      (node (ref "R16") (pin "2") (pinfunction "2_2") (pintype "passive"))
      (node (ref "R17") (pin "2") (pinfunction "2_2") (pintype "passive"))
      (node (ref "SECURSW") (pin "1") (pinfunction "1_1") (pintype "passive"))
    )
    (net (code "38") (name "Net-(R22-Pad1)") (class "Default")
      (node (ref "R22") (pin "1") (pinfunction "1_1") (pintype "passive"))
      (node (ref "T5") (pin "B") (pinfunction "B_B") (pintype "passive"))
    )
    (net (code "39") (name "Net-(R31-Pad2)") (class "Default")
      (node (ref "R31") (pin "2") (pinfunction "2_2") (pintype "passive"))
      (node (ref "T4") (pin "C") (pinfunction "C_C") (pintype "passive"))
    )
    (net (code "40") (name "Net-(STARTB-S)") (class "Default")
      (node (ref "R30") (pin "1") (pinfunction "1_1") (pintype "passive"))
      (node (ref "START") (pin "2") (pinfunction "S_2") (pintype "passive"))
    )
    (net (code "41") (name "Net-(STOPB-S)") (class "Default")
      (node (ref "R31") (pin "1") (pinfunction "1_1") (pintype "passive"))
      (node (ref "STOP") (pin "2") (pinfunction "S_2") (pintype "passive"))
    )
    (net (code "42") (name "Net-(U1A-QC)") (class "Default")
      (node (ref "R21") (pin "1") (pinfunction "1_1") (pintype "passive"))
      (node (ref "U1") (pin "5") (pinfunction "QC_5") (pintype "output"))
    )
    (net (code "43") (name "Net-(U1A-QH)") (class "Default")
      (node (ref "U1") (pin "13") (pinfunction "QH_13") (pintype "output"))
      (node (ref "U2") (pin "1") (pinfunction "A_1") (pintype "input"))
      (node (ref "U2") (pin "2") (pinfunction "B_2") (pintype "input"))
    )
    (net (code "44") (name "Net-(U2A-QE)") (class "Default")
      (node (ref "R22") (pin "2") (pinfunction "2_2") (pintype "passive"))
      (node (ref "U2") (pin "10") (pinfunction "QE_10") (pintype "output"))
    )
    (net (code "45") (name "Net-(U3A-QH)") (class "Default")
      (node (ref "U3") (pin "9") (pinfunction "QH_9") (pintype "output"))
      (node (ref "U4") (pin "5") (pinfunction "I1_5") (pintype "input"))
    )
    (net (code "46") (name "Net-(U4A-I0)") (class "Default")
      (node (ref "U4") (pin "1") (pinfunction "I0_1") (pintype "input"))
      (node (ref "U4") (pin "8") (pinfunction "O_8") (pintype "output"))
    )
    (net (code "47") (name "Net-(U4A-I1)") (class "Default")
      (node (ref "U4") (pin "2") (pinfunction "I1_2") (pintype "input"))
      (node (ref "U4") (pin "6") (pinfunction "O_6") (pintype "output"))
    )
    (net (code "48") (name "Net-(U4B-I0)") (class "Default")
      (node (ref "U4") (pin "11") (pinfunction "O_11") (pintype "output"))
      (node (ref "U4") (pin "4") (pinfunction "I0_4") (pintype "input"))
    )
    (net (code "49") (name "Net-(U5A-I)") (class "Default")
      (node (ref "C3") (pin "2") (pinfunction "2_2") (pintype "passive"))
      (node (ref "R15") (pin "1") (pinfunction "1_1") (pintype "passive"))
      (node (ref "U5") (pin "2") (pinfunction "I_2") (pintype "input"))
    )
    (net (code "50") (name "Net-(U6-AO)") (class "Default")
      (node (ref "R18") (pin "2") (pinfunction "2_2") (pintype "passive"))
      (node (ref "SJ2") (pin "1") (pinfunction "1_1") (pintype "passive"))
      (node (ref "U6") (pin "6") (pinfunction "AO_6") (pintype "bidirectional"))
    )
    (net (code "51") (name "Net-(U6-SCL)") (class "Default")
      (node (ref "R20") (pin "1") (pinfunction "1_1") (pintype "passive"))
      (node (ref "U6") (pin "5") (pinfunction "SCL_5") (pintype "bidirectional"))
      (node (ref "U7") (pin "3") (pinfunction "SCL1_3") (pintype "input"))
    )
    (net (code "52") (name "Net-(U6-SDA)") (class "Default")
      (node (ref "R19") (pin "1") (pinfunction "1_1") (pintype "passive"))
      (node (ref "U6") (pin "4") (pinfunction "SDA_4") (pintype "bidirectional"))
      (node (ref "U7") (pin "2") (pinfunction "SDA1_2") (pintype "input"))
    )
    (net (code "53") (name "ONEWIRE") (class "Default")
      (node (ref "M1") (pin "J6.8") (pinfunction "PC0_J6.8") (pintype "bidirectional"))
      (node (ref "R24") (pin "1") (pinfunction "1_1") (pintype "passive"))
      (node (ref "TEMP") (pin "2") (pinfunction "S_2") (pintype "passive"))
    )
    (net (code "54") (name "RPM_SENSOR") (class "Default")
      (node (ref "M1") (pin "J7.2") (pinfunction "PB0_J7.2") (pintype "bidirectional"))
      (node (ref "U5") (pin "4") (pinfunction "O_4") (pintype "output"))
    )
    (net (code "55") (name "RST") (class "Default")
      (node (ref "ISP") (pin "1") (pinfunction "S_1") (pintype "passive"))
      (node (ref "M1") (pin "J6.3") (pinfunction "RST.1_J6.3") (pintype "bidirectional"))
      (node (ref "M1") (pin "J7.10") (pinfunction "RST.2_J7.10") (pintype "bidirectional"))
    )
    (net (code "56") (name "SCK") (class "Default")
      (node (ref "ISP") (pin "2") (pinfunction "S_2") (pintype "passive"))
      (node (ref "M1") (pin "J6.9") (pinfunction "SCK/PB5_J6.9") (pintype "bidirectional"))
    )
    (net (code "57") (name "SCL") (class "Default")
      (node (ref "DISPLAY") (pin "3") (pinfunction "S_3") (pintype "passive"))
      (node (ref "M1") (pin "J2.2") (pinfunction "SCL/PC5_J2.2") (pintype "bidirectional"))
      (node (ref "R9") (pin "2") (pinfunction "2_2") (pintype "passive"))
      (node (ref "U7") (pin "6") (pinfunction "SCL2_6") (pintype "output"))
    )
    (net (code "58") (name "SDA") (class "Default")
      (node (ref "DISPLAY") (pin "4") (pinfunction "S_4") (pintype "passive"))
      (node (ref "M1") (pin "J2.1") (pinfunction "SDA/PC4_J2.1") (pintype "bidirectional"))
      (node (ref "R10") (pin "2") (pinfunction "2_2") (pintype "passive"))
      (node (ref "U7") (pin "7") (pinfunction "SDA2_7") (pintype "output"))
    )
    (net (code "59") (name "SECURITY_SW") (class "Default")
      (node (ref "C4") (pin "1") (pinfunction "1_1") (pintype "passive"))
      (node (ref "M1") (pin "J7.8") (pinfunction "PD2/INT0_J7.8") (pintype "bidirectional"))
      (node (ref "R17") (pin "1") (pinfunction "1_1") (pintype "passive"))
    )
    (net (code "60") (name "SH{slash}LD_SWITCH") (class "Default")
      (node (ref "J3") (pin "6") (pinfunction "S_6") (pintype "passive"))
      (node (ref "J4") (pin "2") (pinfunction "S_2") (pintype "passive"))
      (node (ref "U3") (pin "1") (pinfunction "SH/~{LD}_1") (pintype "input"))
    )
    (net (code "61") (name "SMC_LED") (class "Default")
      (node (ref "M1") (pin "J7.3") (pinfunction "PD7_J7.3") (pintype "bidirectional"))
      (node (ref "OK1") (pin "4") (pinfunction "COL_4") (pintype "passive"))
    )
    (net (code "62") (name "SMC_SW") (class "Default")
      (node (ref "M1") (pin "J7.4") (pinfunction "PD6/OC0A_J7.4") (pintype "bidirectional"))
      (node (ref "R4") (pin "2") (pinfunction "2_2") (pintype "passive"))
    )
    (net (code "63") (name "STARTLED") (class "Default")
      (node (ref "R30") (pin "2") (pinfunction "2_2") (pintype "passive"))
      (node (ref "T3") (pin "C") (pinfunction "C_C") (pintype "passive"))
    )
    (net (code "64") (name "START_LED_") (class "Default")
      (node (ref "ISP") (pin "4") (pinfunction "S_4") (pintype "passive"))
      (node (ref "M1") (pin "J6.11") (pinfunction "MOSI/PB3_J6.11") (pintype "bidirectional"))
      (node (ref "R2") (pin "2") (pinfunction "2_2") (pintype "passive"))
    )
    (net (code "65") (name "START_SW") (class "Default")
      (node (ref "M1") (pin "J7.6") (pinfunction "PD4_J7.6") (pintype "bidirectional"))
      (node (ref "START") (pin "4") (pinfunction "S_4") (pintype "passive"))
    )
    (net (code "66") (name "STOP_LED_") (class "Default")
      (node (ref "M1") (pin "J6.12") (pinfunction "OC1B/PB2_J6.12") (pintype "bidirectional"))
      (node (ref "R3") (pin "2") (pinfunction "2_2") (pintype "passive"))
    )
    (net (code "67") (name "STOP_SW") (class "Default")
      (node (ref "M1") (pin "J7.7") (pinfunction "PD3/INT1_J7.7") (pintype "bidirectional"))
      (node (ref "STOP") (pin "4") (pinfunction "S_4") (pintype "passive"))
    )
    (net (code "68") (name "VOUT") (class "Default")
      (node (ref "J9") (pin "2") (pinfunction "S_2") (pintype "passive"))
      (node (ref "J9A-") (pin "2") (pinfunction "1_2") (pintype "passive"))
      (node (ref "U6") (pin "1") (pinfunction "VOUT_1") (pintype "bidirectional"))
    )
    (net (code "69") (name "unconnected-(F2-Pad1B)") (class "Default")
      (node (ref "F2") (pin "1B") (pinfunction "1B_1B") (pintype "passive"))
    )
    (net (code "70") (name "unconnected-(F2-Pad2B)") (class "Default")
      (node (ref "F2") (pin "2B") (pinfunction "2B_2B") (pintype "passive"))
    )
    (net (code "71") (name "unconnected-(M1-ADC7-PadJ3.3)") (class "Default")
      (node (ref "M1") (pin "J3.3") (pinfunction "ADC7_J3.3") (pintype "bidirectional"))
    )
    (net (code "72") (name "unconnected-(M1-PD0{slash}RX-PadJ7.11)") (class "Default")
      (node (ref "M1") (pin "J7.11") (pinfunction "PD0/RX_J7.11") (pintype "bidirectional"))
    )
    (net (code "73") (name "unconnected-(M1-PD1{slash}TX-PadJ7.12)") (class "Default")
      (node (ref "M1") (pin "J7.12") (pinfunction "PD1/TX_J7.12") (pintype "bidirectional"))
    )
    (net (code "74") (name "unconnected-(M1-P_CTS-PadJ1.5)") (class "Default")
      (node (ref "M1") (pin "J1.5") (pinfunction "P_CTS_J1.5") (pintype "bidirectional"))
    )
    (net (code "75") (name "unconnected-(M1-P_DTR-PadJ1.1)") (class "Default")
      (node (ref "M1") (pin "J1.1") (pinfunction "P_DTR_J1.1") (pintype "bidirectional"))
    )
    (net (code "76") (name "unconnected-(M1-P_RXD-PadJ1.2)") (class "Default")
      (node (ref "M1") (pin "J1.2") (pinfunction "P_RXD_J1.2") (pintype "bidirectional"))
    )
    (net (code "77") (name "unconnected-(M1-P_TXD-PadJ1.3)") (class "Default")
      (node (ref "M1") (pin "J1.3") (pinfunction "P_TXD_J1.3") (pintype "bidirectional"))
    )
    (net (code "78") (name "unconnected-(U1A-QA-Pad3)") (class "Default")
      (node (ref "U1") (pin "3") (pinfunction "QA_3") (pintype "output"))
    )
    (net (code "79") (name "unconnected-(U1A-QB-Pad4)") (class "Default")
      (node (ref "U1") (pin "4") (pinfunction "QB_4") (pintype "output"))
    )
    (net (code "80") (name "unconnected-(U1A-QD-Pad6)") (class "Default")
      (node (ref "U1") (pin "6") (pinfunction "QD_6") (pintype "output"))
    )
    (net (code "81") (name "unconnected-(U1A-QE-Pad10)") (class "Default")
      (node (ref "U1") (pin "10") (pinfunction "QE_10") (pintype "output"))
    )
    (net (code "82") (name "unconnected-(U1A-QF-Pad11)") (class "Default")
      (node (ref "U1") (pin "11") (pinfunction "QF_11") (pintype "output"))
    )
    (net (code "83") (name "unconnected-(U1A-QG-Pad12)") (class "Default")
      (node (ref "U1") (pin "12") (pinfunction "QG_12") (pintype "output"))
    )
    (net (code "84") (name "unconnected-(U2A-QA-Pad3)") (class "Default")
      (node (ref "U2") (pin "3") (pinfunction "QA_3") (pintype "output"))
    )
    (net (code "85") (name "unconnected-(U2A-QB-Pad4)") (class "Default")
      (node (ref "U2") (pin "4") (pinfunction "QB_4") (pintype "output"))
    )
    (net (code "86") (name "unconnected-(U2A-QC-Pad5)") (class "Default")
      (node (ref "U2") (pin "5") (pinfunction "QC_5") (pintype "output"))
    )
    (net (code "87") (name "unconnected-(U2A-QD-Pad6)") (class "Default")
      (node (ref "U2") (pin "6") (pinfunction "QD_6") (pintype "output"))
    )
    (net (code "88") (name "unconnected-(U2A-QF-Pad11)") (class "Default")
      (node (ref "U2") (pin "11") (pinfunction "QF_11") (pintype "output"))
    )
    (net (code "89") (name "unconnected-(U2A-QG-Pad12)") (class "Default")
      (node (ref "U2") (pin "12") (pinfunction "QG_12") (pintype "output"))
    )
    (net (code "90") (name "unconnected-(U2A-QH-Pad13)") (class "Default")
      (node (ref "U2") (pin "13") (pinfunction "QH_13") (pintype "output"))
    )
    (net (code "91") (name "unconnected-(U3A-~{QH}-Pad7)") (class "Default")
      (node (ref "U3") (pin "7") (pinfunction "~{QH}_7") (pintype "output"))
    )
  )
)
